# 3_-_STM32F103_Debugger.net
KiCad netlist of a schematic drawn in Altium Designer
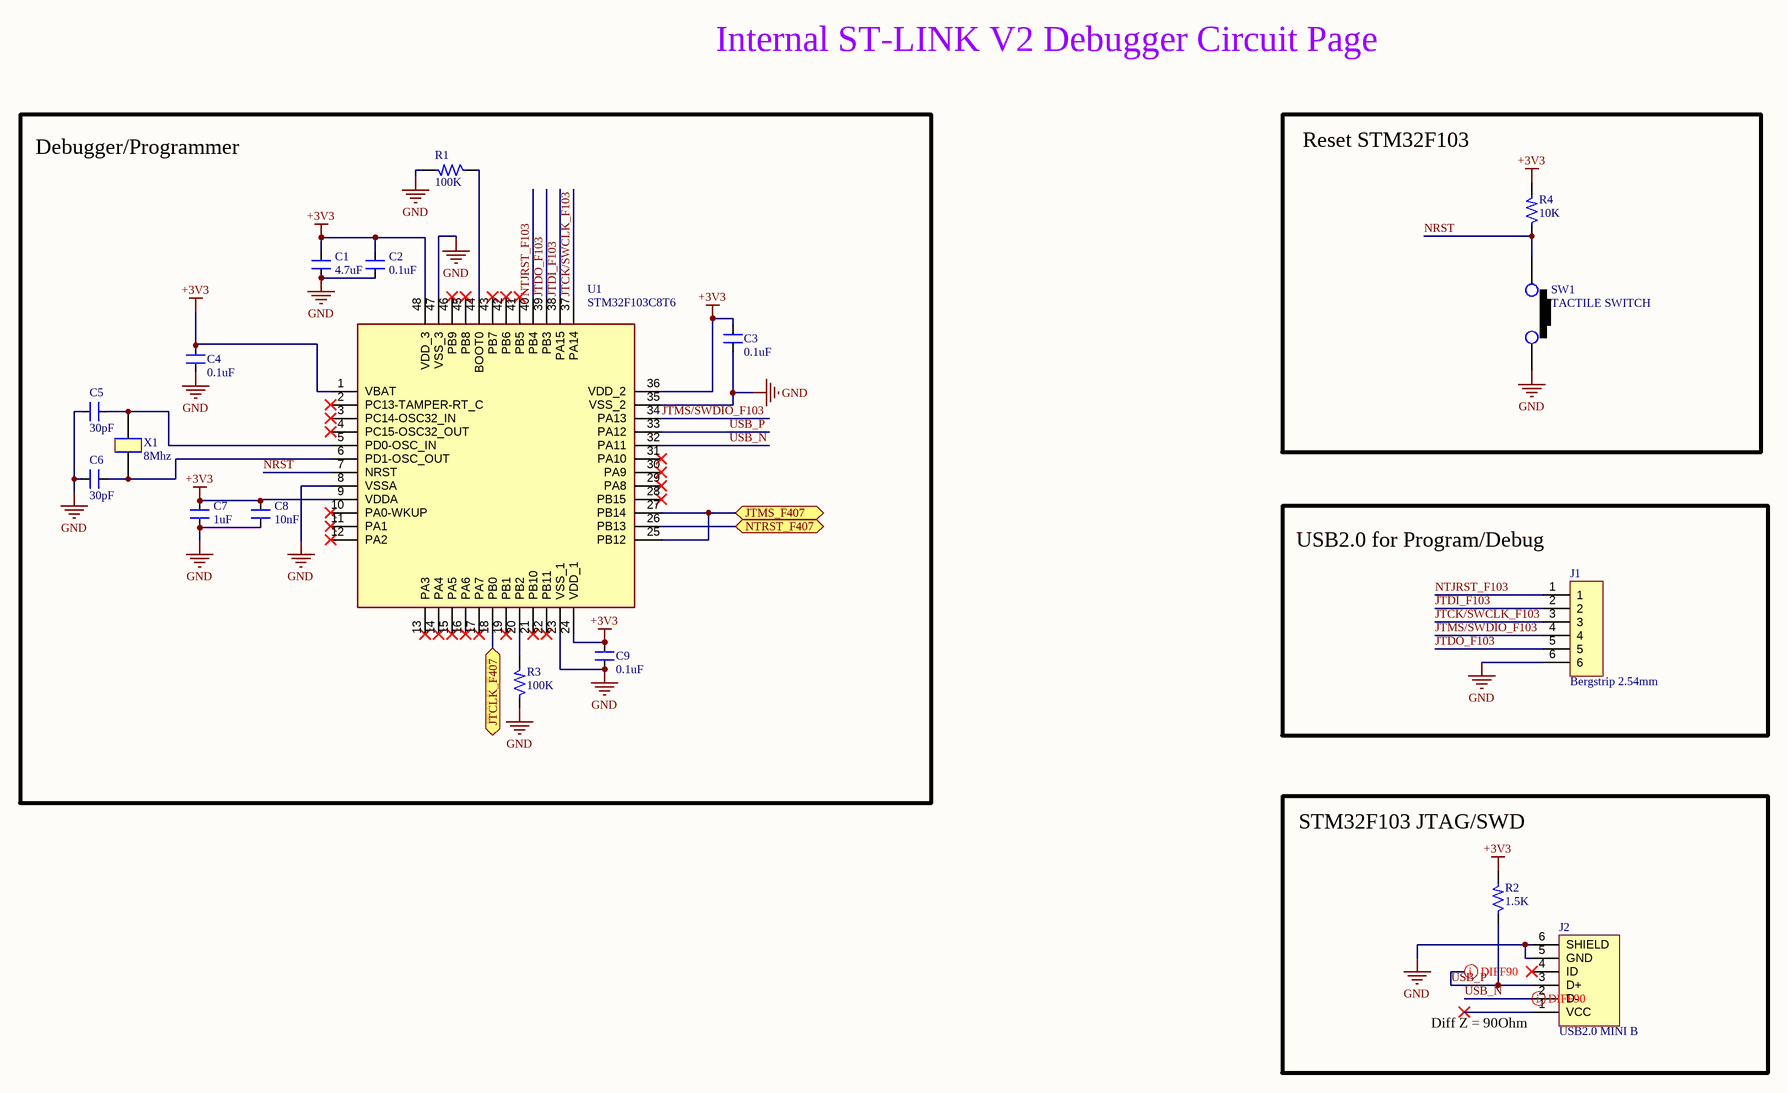
[diagram p0: [3] - STM32F103 Debugger.SchDoc]

(export (version "E")
  (design (tool "Eeschema 10.0.6"))
  (components
    (comp (ref "C1")
      (value "4.7uF")
      (footprint "CAP_0805")
      (description "4.7µF ±10% 50V Ceramic Capacitor X5R 0805 (2012 Metric)")
      (fields
        (field (name "MANUFACTURER") "Yageo")
        (field (name "MANUFACTURER PART NUMBER") "GRM21BR61H475KE51L")
      )
      (libsource (lib "ESTEEMPCBLIB") (part "CAP_4.7uF-50V-10%-0805"))
    )
    (comp (ref "C2")
      (value "0.1uF")
      (footprint "CAP_0805")
      (description "0.1µF ±10% 50V Ceramic Capacitor X7R 0805 (2012 Metric)")
      (fields
        (field (name "MANUFACTURER") "Samsung")
        (field (name "MANUFACTURER PART NUMBER") "CL21B104KBCNNNC")
      )
      (libsource (lib "ESTEEMPCBLIB") (part "CAP_0.1uF-50V-10%-0805"))
    )
    (comp (ref "C3")
      (value "0.1uF")
      (footprint "CAP_0805")
      (description "0.1µF ±10% 50V Ceramic Capacitor X7R 0805 (2012 Metric)")
      (fields
        (field (name "MANUFACTURER") "Samsung")
        (field (name "MANUFACTURER PART NUMBER") "CL21B104KBCNNNC")
      )
      (libsource (lib "ESTEEMPCBLIB") (part "CAP_0.1uF-50V-10%-0805"))
    )
    (comp (ref "C4")
      (value "0.1uF")
      (footprint "CAP_0805")
      (description "0.1µF ±10% 50V Ceramic Capacitor X7R 0805 (2012 Metric)")
      (fields
        (field (name "MANUFACTURER") "Samsung")
        (field (name "MANUFACTURER PART NUMBER") "CL21B104KBCNNNC")
      )
      (libsource (lib "ESTEEMPCBLIB") (part "CAP_0.1uF-50V-10%-0805"))
    )
    (comp (ref "C5")
      (value "30pF")
      (footprint "CAP_0805")
      (description "±10% 50V Ceramic Capacitor C0G, NP0 0805 (2012 Metric)")
      (fields
        (field (name "MANUFACTURER PART NUMBER") "C0805C300K5GAC7800")
        (field (name "MANUFACTURER") "KEMET")
      )
      (libsource (lib "ESTEEMPCBLIB") (part "CAP_30pF-50V-10%-0805"))
    )
    (comp (ref "C6")
      (value "30pF")
      (footprint "CAP_0805")
      (description "±10% 50V Ceramic Capacitor C0G, NP0 0805 (2012 Metric)")
      (fields
        (field (name "MANUFACTURER PART NUMBER") "C0805C300K5GAC7800")
        (field (name "MANUFACTURER") "KEMET")
      )
      (libsource (lib "ESTEEMPCBLIB") (part "CAP_30pF-50V-10%-0805"))
    )
    (comp (ref "C7")
      (value "1uF")
      (footprint "CAP_0805")
      (description "1µF ±5% 50V Ceramic Capacitor X7R 0805 (2012 Metric)")
      (fields
        (field (name "MANUFACTURER") "Samsung")
        (field (name "MANUFACTURER PART NUMBER") "CC0805JKX7R9BB105")
      )
      (libsource (lib "ESTEEMPCBLIB") (part "CAP_1uF-50V-5%-0805"))
    )
    (comp (ref "C8")
      (value "10nF")
      (footprint "CAP_0805")
      (description "10000pF ±10% 50V Ceramic Capacitor X7R 0805 (2012 Metric)")
      (fields
        (field (name "MANUFACTURER") "Samsung")
        (field (name "MANUFACTURER PART NUMBER") "C0805C103K5RECAUTO")
      )
      (libsource (lib "ESTEEMPCBLIB") (part "CAP_10nF-50V-10%-0805"))
    )
    (comp (ref "C9")
      (value "0.1uF")
      (footprint "CAP_0805")
      (description "0.1µF ±10% 50V Ceramic Capacitor X7R 0805 (2012 Metric)")
      (fields
        (field (name "MANUFACTURER") "Samsung")
        (field (name "MANUFACTURER PART NUMBER") "CL21B104KBCNNNC")
      )
      (libsource (lib "ESTEEMPCBLIB") (part "CAP_0.1uF-50V-10%-0805"))
    )
    (comp (ref "J1")
      (value "Bergstrip 2.54mm")
      (footprint "CON6_100_59D78_TH_ST")
      (description "6 Pins, 1 Row 2.54mm Pitch, Straight bergstrip, Female")
      (fields (field (name "MANUFACTURER") "Molex") (field (name "MANUFACTURER PART NUMBER") "22-10-2061"))
      (libsource (lib "ESTEEMPCBLIB") (part "CON-BS-SKT_6X1-100-ST-TH"))
    )
    (comp (ref "J2")
      (value "USB2.0 MINI B")
      (footprint "CON_690-005-299-043")
      (description "USB - mini B USB 2.0 Receptacle Connector 5 Position Surface Mount, Right Angle")
      (fields
        (field (name "MANUFACTURER") "EDAC")
        (field (name "MANUFACTURER PART NUMBER") "690-005-299-043")
      )
      (libsource (lib "ESTEEMPCBLIB") (part "CON_USB2.0-MINIB-SMD"))
    )
    (comp (ref "R1")
      (value "100K")
      (footprint "RES_0603")
      (description "100 kOhms ±1% 0.1W, 1/10W Chip Resistor 0603 (1608 Metric) Automotive AEC-Q200 Thick Film")
      (fields
        (field (name "MANUFACTURER") "Stackpole Electronics")
        (field (name "MANUFACTURER PART NUMBER") "RMCF0603FT100K")
      )
      (libsource (lib "ESTEEMPCBLIB") (part "RES_100K-0.1W-1%-0603"))
    )
    (comp (ref "R2")
      (value "1.5K")
      (footprint "RES_0805")
      (description "1.5 kOhms ±1% 0.125W, 1/8W Chip Resistor 0805 (2012 Metric) Thick Film")
      (fields
        (field (name "MANUFACTURER") "TE Connectivity Passive Product")
        (field (name "MANUFACTURER PART NUMBER") "CRG0805F1K5")
      )
      (libsource (lib "ESTEEMPCBLIB") (part "RES_1.5K-0.125W-1%-0805"))
    )
    (comp (ref "R3")
      (value "100K")
      (footprint "RES_0603")
      (description "100 kOhms ±1% 0.1W, 1/10W Chip Resistor 0603 (1608 Metric) Automotive AEC-Q200 Thick Film")
      (fields
        (field (name "MANUFACTURER") "Stackpole Electronics")
        (field (name "MANUFACTURER PART NUMBER") "RMCF0603FT100K")
      )
      (libsource (lib "ESTEEMPCBLIB") (part "RES_100K-0.1W-1%-0603"))
    )
    (comp (ref "R4")
      (value "10K")
      (footprint "RES_0603")
      (description "10 kOhms ±1% 0.1W, 1/10W Chip Resistor 0603 (1608 Metric) Automotive AEC-Q200 Thick Film")
      (fields (field (name "MANUFACTURER") "Walsin") (field (name "MANUFACTURER PART NUMBER") "WR06X1002FTL"))
      (libsource (lib "ESTEEMPCBLIB") (part "RES_10K-0.1W-1%-0603"))
    )
    (comp (ref "SW1")
      (value "TACTILE SWITCH")
      (footprint "SW_342_SMD")
      (description "Tactile Switch SPST-NO Top Actuated Surface Mount")
      (fields
        (field (name "MANUFACTURER") "ITT C&K")
        (field (name "MANUFACTURER PART NUMBER") "RS-282G05A3-SMRT")
      )
      (libsource (lib "ESTEEMPCBLIB") (part "SW1_RS-282G05A3-SMRT-SMD"))
    )
    (comp (ref "U1")
      (value "STM32F103C8T6")
      (footprint "LQFP-48_19.6_393_58X11_SMD")
      (description "ARM® Cortex®-M3 STM32F1 Microcontroller IC 32-Bit 72MHz 64KB (64K x 8) FLASH 48-LQFP (7x7)")
      (fields (field (name "MANUFACTURER") "STMicroelectronics"))
      (libsource (lib "ESTEEMPCBLIB") (part "IC_STM32F103C8T6"))
    )
    (comp (ref "X1")
      (value "8Mhz")
      (footprint "XTAL_314_240X47_SMD")
      (description "8MHz ±30ppm Crystal 32pF 60 Ohms HC-49/US")
      (fields
        (field (name "MANUFACTURER") "Fox Electronics")
        (field (name "MANUFACTURER PART NUMBER") "ECS-80-32-5PX-TR")
      )
      (libsource (lib "ESTEEMPCBLIB") (part "XTAL_8MHZ-ECS-80-32-5PX-SMD"))
    )
  )
  (nets
    (net (code "1") (name "+3V3") (class "Default")
      (node (ref "C1") (pin "2") (pinfunction "2_2") (pintype "passive"))
      (node (ref "C2") (pin "2") (pinfunction "2_2") (pintype "passive"))
      (node (ref "C3") (pin "2") (pinfunction "2_2") (pintype "passive"))
      (node (ref "C4") (pin "2") (pinfunction "2_2") (pintype "passive"))
      (node (ref "C7") (pin "2") (pinfunction "2_2") (pintype "passive"))
      (node (ref "C8") (pin "2") (pinfunction "2_2") (pintype "passive"))
      (node (ref "C9") (pin "2") (pinfunction "2_2") (pintype "passive"))
      (node (ref "R2") (pin "2") (pinfunction "2_2") (pintype "passive"))
      (node (ref "R4") (pin "2") (pinfunction "2_2") (pintype "passive"))
      (node (ref "U1") (pin "1") (pinfunction "VBAT_1") (pintype "passive"))
      (node (ref "U1") (pin "24") (pinfunction "VDD_1_24") (pintype "passive"))
      (node (ref "U1") (pin "36") (pinfunction "VDD_2_36") (pintype "passive"))
      (node (ref "U1") (pin "48") (pinfunction "VDD_3_48") (pintype "passive"))
      (node (ref "U1") (pin "9") (pinfunction "VDDA_9") (pintype "passive"))
    )
    (net (code "2") (name "/JTCK{slash}SWCLK_F103") (class "Default")
      (node (ref "J1") (pin "3") (pinfunction "3_3") (pintype "passive"))
      (node (ref "U1") (pin "37") (pinfunction "PA14_37") (pintype "passive"))
    )
    (net (code "3") (name "/JTCLK_F407") (class "Default")
      (node (ref "U1") (pin "18") (pinfunction "PB0_18") (pintype "passive"))
    )
    (net (code "4") (name "/JTDI_F103") (class "Default")
      (node (ref "J1") (pin "2") (pinfunction "2_2") (pintype "passive"))
      (node (ref "U1") (pin "38") (pinfunction "PA15_38") (pintype "passive"))
    )
    (net (code "5") (name "/JTDO_F103") (class "Default")
      (node (ref "J1") (pin "5") (pinfunction "5_5") (pintype "passive"))
      (node (ref "U1") (pin "39") (pinfunction "PB3_39") (pintype "passive"))
    )
    (net (code "6") (name "/JTMS_F407") (class "Default")
      (node (ref "U1") (pin "25") (pinfunction "PB12_25") (pintype "passive"))
      (node (ref "U1") (pin "27") (pinfunction "PB14_27") (pintype "passive"))
    )
    (net (code "7") (name "/JTMS{slash}SWDIO_F103") (class "Default")
      (node (ref "J1") (pin "4") (pinfunction "4_4") (pintype "passive"))
      (node (ref "U1") (pin "34") (pinfunction "PA13_34") (pintype "passive"))
    )
    (net (code "8") (name "/NRST") (class "Default")
      (node (ref "R4") (pin "1") (pinfunction "1_1") (pintype "passive"))
      (node (ref "SW1") (pin "1") (pinfunction "1_1") (pintype "passive"))
      (node (ref "U1") (pin "7") (pinfunction "NRST_7") (pintype "passive"))
    )
    (net (code "9") (name "/NTJRST_F103") (class "Default")
      (node (ref "J1") (pin "1") (pinfunction "1_1") (pintype "passive"))
      (node (ref "U1") (pin "40") (pinfunction "PB4_40") (pintype "passive"))
    )
    (net (code "10") (name "/NTRST_F407") (class "Default")
      (node (ref "U1") (pin "26") (pinfunction "PB13_26") (pintype "passive"))
    )
    (net (code "11") (name "/USB_N") (class "Default")
      (node (ref "J2") (pin "2") (pinfunction "D-_2") (pintype "passive"))
      (node (ref "U1") (pin "32") (pinfunction "PA11_32") (pintype "passive"))
    )
    (net (code "12") (name "/USB_P") (class "Default")
      (node (ref "J2") (pin "3") (pinfunction "D+_3") (pintype "passive"))
      (node (ref "R2") (pin "1") (pinfunction "1_1") (pintype "passive"))
      (node (ref "U1") (pin "33") (pinfunction "PA12_33") (pintype "passive"))
    )
    (net (code "13") (name "GND") (class "Default")
      (node (ref "C1") (pin "1") (pinfunction "1_1") (pintype "passive"))
      (node (ref "C2") (pin "1") (pinfunction "1_1") (pintype "passive"))
      (node (ref "C3") (pin "1") (pinfunction "1_1") (pintype "passive"))
      (node (ref "C4") (pin "1") (pinfunction "1_1") (pintype "passive"))
      (node (ref "C5") (pin "1") (pinfunction "1_1") (pintype "passive"))
      (node (ref "C6") (pin "1") (pinfunction "1_1") (pintype "passive"))
      (node (ref "C7") (pin "1") (pinfunction "1_1") (pintype "passive"))
      (node (ref "C8") (pin "1") (pinfunction "1_1") (pintype "passive"))
      (node (ref "C9") (pin "1") (pinfunction "1_1") (pintype "passive"))
      (node (ref "J1") (pin "6") (pinfunction "6_6") (pintype "passive"))
      (node (ref "J2") (pin "5") (pinfunction "GND_5") (pintype "passive"))
      (node (ref "J2") (pin "6") (pinfunction "SHIELD_6") (pintype "passive"))
      (node (ref "R1") (pin "2") (pinfunction "2_2") (pintype "passive"))
      (node (ref "R3") (pin "1") (pinfunction "1_1") (pintype "passive"))
      (node (ref "SW1") (pin "2") (pinfunction "2_2") (pintype "passive"))
      (node (ref "U1") (pin "23") (pinfunction "VSS_1_23") (pintype "passive"))
      (node (ref "U1") (pin "35") (pinfunction "VSS_2_35") (pintype "passive"))
      (node (ref "U1") (pin "47") (pinfunction "VSS_3_47") (pintype "passive"))
      (node (ref "U1") (pin "8") (pinfunction "VSSA_8") (pintype "passive"))
    )
    (net (code "14") (name "Net-(U1-BOOT0)") (class "Default")
      (node (ref "R1") (pin "1") (pinfunction "1_1") (pintype "passive"))
      (node (ref "U1") (pin "44") (pinfunction "BOOT0_44") (pintype "passive"))
    )
    (net (code "15") (name "Net-(U1-PB2)") (class "Default")
      (node (ref "R3") (pin "2") (pinfunction "2_2") (pintype "passive"))
      (node (ref "U1") (pin "20") (pinfunction "PB2_20") (pintype "passive"))
    )
    (net (code "16") (name "Net-(U1-PD0-OSC_IN)") (class "Default")
      (node (ref "C5") (pin "2") (pinfunction "2_2") (pintype "passive"))
      (node (ref "U1") (pin "5") (pinfunction "PD0-OSC_IN_5") (pintype "passive"))
      (node (ref "X1") (pin "2") (pinfunction "2_2") (pintype "passive"))
    )
    (net (code "17") (name "Net-(U1-PD1-OSC_OUT)") (class "Default")
      (node (ref "C6") (pin "2") (pinfunction "2_2") (pintype "passive"))
      (node (ref "U1") (pin "6") (pinfunction "PD1-OSC_OUT_6") (pintype "passive"))
      (node (ref "X1") (pin "1") (pinfunction "1_1") (pintype "passive"))
    )
    (net (code "18") (name "unconnected-(J2-ID-Pad4)") (class "Default")
      (node (ref "J2") (pin "4") (pinfunction "ID_4") (pintype "passive+no_connect"))
    )
    (net (code "19") (name "unconnected-(J2-VCC-Pad1)") (class "Default")
      (node (ref "J2") (pin "1") (pinfunction "VCC_1") (pintype "passive+no_connect"))
    )
    (net (code "20") (name "unconnected-(U1-PA0-WKUP-Pad10)") (class "Default")
      (node (ref "U1") (pin "10") (pinfunction "PA0-WKUP_10") (pintype "passive+no_connect"))
    )
    (net (code "21") (name "unconnected-(U1-PA1-Pad11)") (class "Default")
      (node (ref "U1") (pin "11") (pinfunction "PA1_11") (pintype "passive+no_connect"))
    )
    (net (code "22") (name "unconnected-(U1-PA2-Pad12)") (class "Default")
      (node (ref "U1") (pin "12") (pinfunction "PA2_12") (pintype "passive+no_connect"))
    )
    (net (code "23") (name "unconnected-(U1-PA3-Pad13)") (class "Default")
      (node (ref "U1") (pin "13") (pinfunction "PA3_13") (pintype "passive+no_connect"))
    )
    (net (code "24") (name "unconnected-(U1-PA4-Pad14)") (class "Default")
      (node (ref "U1") (pin "14") (pinfunction "PA4_14") (pintype "passive+no_connect"))
    )
    (net (code "25") (name "unconnected-(U1-PA5-Pad15)") (class "Default")
      (node (ref "U1") (pin "15") (pinfunction "PA5_15") (pintype "passive+no_connect"))
    )
    (net (code "26") (name "unconnected-(U1-PA6-Pad16)") (class "Default")
      (node (ref "U1") (pin "16") (pinfunction "PA6_16") (pintype "passive+no_connect"))
    )
    (net (code "27") (name "unconnected-(U1-PA7-Pad17)") (class "Default")
      (node (ref "U1") (pin "17") (pinfunction "PA7_17") (pintype "passive+no_connect"))
    )
    (net (code "28") (name "unconnected-(U1-PA8-Pad29)") (class "Default")
      (node (ref "U1") (pin "29") (pinfunction "PA8_29") (pintype "passive+no_connect"))
    )
    (net (code "29") (name "unconnected-(U1-PA9-Pad30)") (class "Default")
      (node (ref "U1") (pin "30") (pinfunction "PA9_30") (pintype "passive+no_connect"))
    )
    (net (code "30") (name "unconnected-(U1-PA10-Pad31)") (class "Default")
      (node (ref "U1") (pin "31") (pinfunction "PA10_31") (pintype "passive+no_connect"))
    )
    (net (code "31") (name "unconnected-(U1-PB1-Pad19)") (class "Default")
      (node (ref "U1") (pin "19") (pinfunction "PB1_19") (pintype "passive+no_connect"))
    )
    (net (code "32") (name "unconnected-(U1-PB5-Pad41)") (class "Default")
      (node (ref "U1") (pin "41") (pinfunction "PB5_41") (pintype "passive+no_connect"))
    )
    (net (code "33") (name "unconnected-(U1-PB6-Pad42)") (class "Default")
      (node (ref "U1") (pin "42") (pinfunction "PB6_42") (pintype "passive+no_connect"))
    )
    (net (code "34") (name "unconnected-(U1-PB7-Pad43)") (class "Default")
      (node (ref "U1") (pin "43") (pinfunction "PB7_43") (pintype "passive+no_connect"))
    )
    (net (code "35") (name "unconnected-(U1-PB8-Pad45)") (class "Default")
      (node (ref "U1") (pin "45") (pinfunction "PB8_45") (pintype "passive+no_connect"))
    )
    (net (code "36") (name "unconnected-(U1-PB9-Pad46)") (class "Default")
      (node (ref "U1") (pin "46") (pinfunction "PB9_46") (pintype "passive+no_connect"))
    )
    (net (code "37") (name "unconnected-(U1-PB10-Pad21)") (class "Default")
      (node (ref "U1") (pin "21") (pinfunction "PB10_21") (pintype "passive+no_connect"))
    )
    (net (code "38") (name "unconnected-(U1-PB11-Pad22)") (class "Default")
      (node (ref "U1") (pin "22") (pinfunction "PB11_22") (pintype "passive+no_connect"))
    )
    (net (code "39") (name "unconnected-(U1-PB15-Pad28)") (class "Default")
      (node (ref "U1") (pin "28") (pinfunction "PB15_28") (pintype "passive+no_connect"))
    )
    (net (code "40") (name "unconnected-(U1-PC13-TAMPER-RT_C-Pad2)") (class "Default")
      (node (ref "U1") (pin "2") (pinfunction "PC13-TAMPER-RT_C_2") (pintype "passive+no_connect"))
    )
    (net (code "41") (name "unconnected-(U1-PC14-OSC32_IN-Pad3)") (class "Default")
      (node (ref "U1") (pin "3") (pinfunction "PC14-OSC32_IN_3") (pintype "passive+no_connect"))
    )
    (net (code "42") (name "unconnected-(U1-PC15-OSC32_OUT-Pad4)") (class "Default")
      (node (ref "U1") (pin "4") (pinfunction "PC15-OSC32_OUT_4") (pintype "passive+no_connect"))
    )
  )
)
